# 2_Power_Switch.net
KiCad netlist of a schematic drawn in Altium Designer
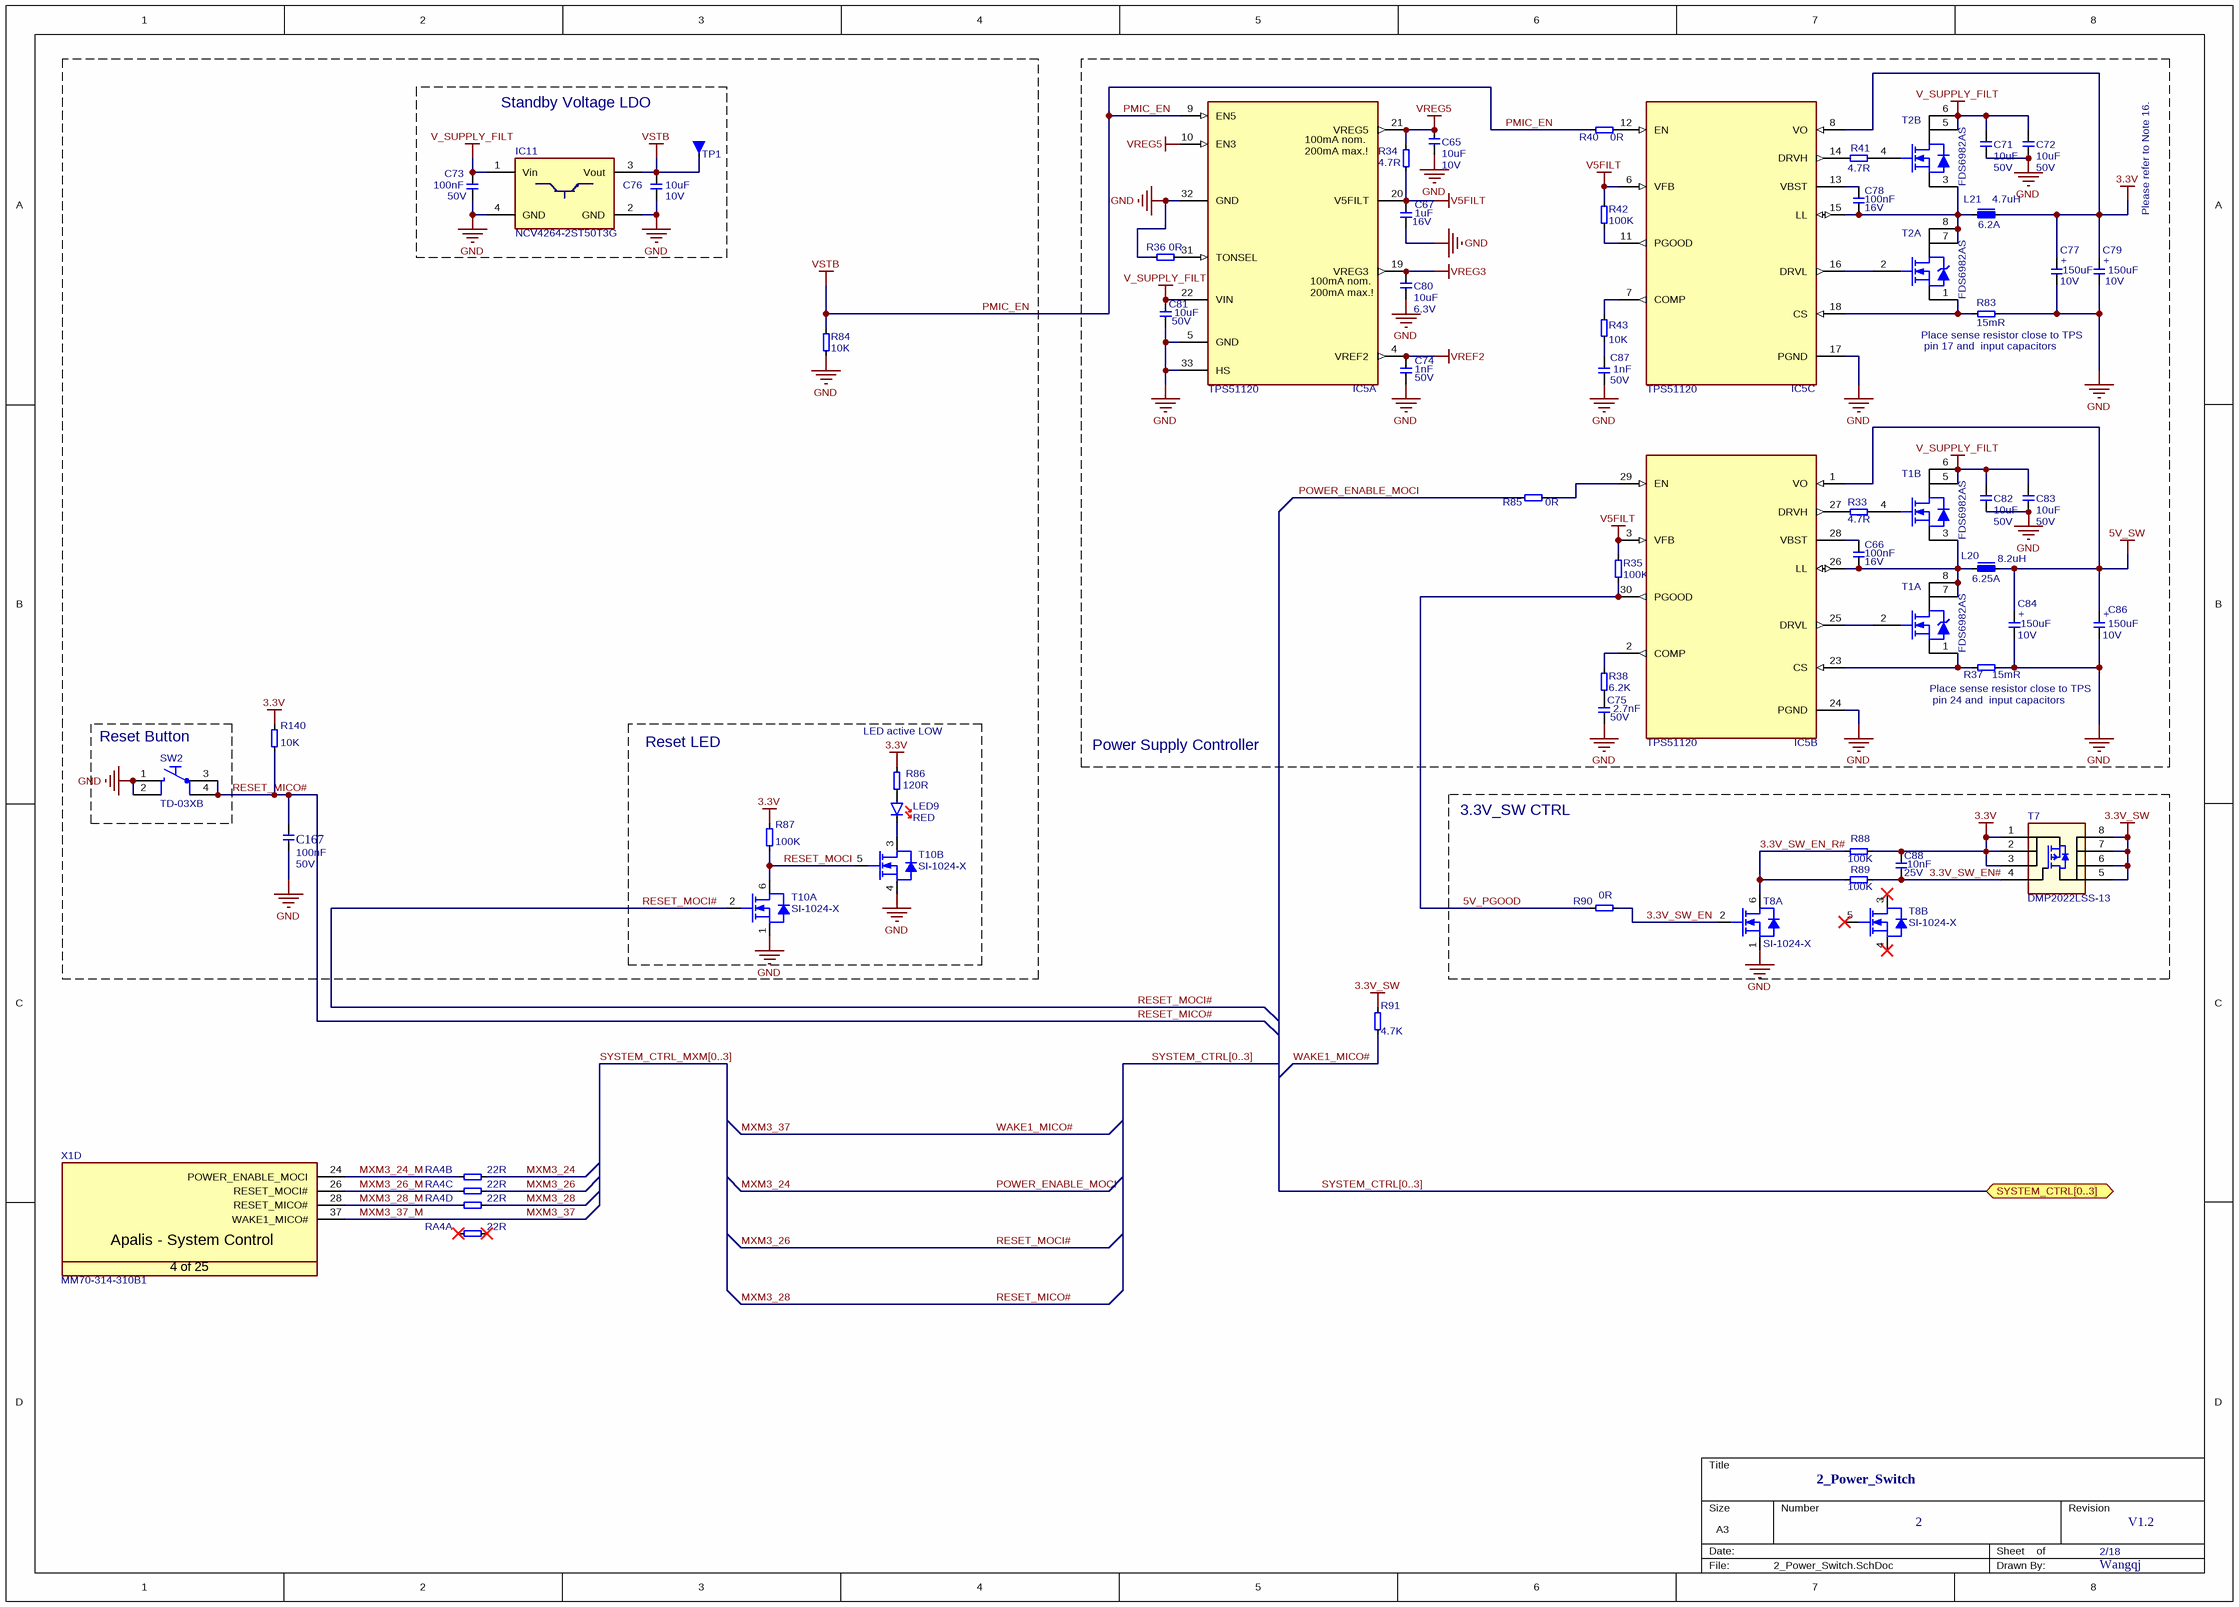
[diagram p0: 2_Power_Switch.SchDoc]

(export (version "E")
  (design (tool "Eeschema 10.0.6"))
  (components
    (comp (ref "C65")
      (value "10uF")
      (footprint "T_CAPC0805X125N")
      (description "Capacitor Ceramic X5R 10uF 10V 20% 0805")
      (fields (field (name "TOLERANCE") "20%") (field (name "RATING") "10V"))
      (libsource (lib "Apalis Evaluation Board") (part "C-X5R-10uF-10V-20%-0805"))
    )
    (comp (ref "C66")
      (value "100nF")
      (footprint "T_CAPC0603X33N")
      (description "Capacitor Ceramic X7R 100nF 16V 10% 0603")
      (fields (field (name "TOLERANCE") "10%") (field (name "RATING") "16V"))
      (libsource (lib "Apalis Evaluation Board") (part "C-X7R-100nF-16V-10%-0603"))
    )
    (comp (ref "C67")
      (value "1uF")
      (footprint "T_CAPC0603X33N")
      (description "Capacitor Ceramic X5R 1uF 16V 20% 0603")
      (fields (field (name "TOLERANCE") "20%") (field (name "RATING") "16V"))
      (libsource (lib "Apalis Evaluation Board") (part "C-X5R-1uF-16V-20%-0603"))
    )
    (comp (ref "C71")
      (value "10uF")
      (footprint "CAPC3225X160N")
      (description "Capacitor Ceramic X5R 10uF 50V 20% 1210")
      (fields (field (name "TOLERANCE") "20%") (field (name "RATING") "50V"))
      (libsource (lib "Apalis Evaluation Board") (part "C-X5R-10uF-50V-20%-1210"))
    )
    (comp (ref "C72")
      (value "10uF")
      (footprint "CAPC3225X160N")
      (description "Capacitor Ceramic X5R 10uF 50V 20% 1210")
      (fields (field (name "TOLERANCE") "20%") (field (name "RATING") "50V"))
      (libsource (lib "Apalis Evaluation Board") (part "C-X5R-10uF-50V-20%-1210"))
    )
    (comp (ref "C73")
      (value "100nF")
      (footprint "T_CAPC0603X33N")
      (description "Capacitor Ceramic X7R 100nF 50V 20% 0603")
      (fields (field (name "TOLERANCE") "20%") (field (name "RATING") "50V"))
      (libsource (lib "Apalis Evaluation Board") (part "C-X7R-100nF-50V-20%-0603"))
    )
    (comp (ref "C74")
      (value "1nF")
      (footprint "T_CAPC0603X33N")
      (description "Capacitor Ceramic X7R 1nF 50V 10% 0603")
      (fields (field (name "TOLERANCE") "10%") (field (name "RATING") "50V"))
      (libsource (lib "Apalis Evaluation Board") (part "C-X7R-1nF-50V-10%-0603"))
    )
    (comp (ref "C75")
      (value "2.7nF")
      (footprint "CAPC1005X60N")
      (description "Capacitor Ceramic X7R 2.7nF 50V 10% 0402")
      (fields (field (name "TOLERANCE") "10%") (field (name "RATING") "50V"))
      (libsource (lib "Apalis Evaluation Board") (part "C-X7R-2.7nF-50V-10%-0402"))
    )
    (comp (ref "C76")
      (value "10uF")
      (footprint "T_CAPC0805X125N")
      (description "Capacitor Ceramic X5R 10uF 10V 20% 0805")
      (fields (field (name "TOLERANCE") "20%") (field (name "RATING") "10V"))
      (libsource (lib "Apalis Evaluation Board") (part "C-X5R-10uF-10V-20%-0805"))
    )
    (comp (ref "C77")
      (value "150uF")
      (footprint "CAPMP7343X310N")
      (description "Capacitor TA 150uF 10V 10% 7343")
      (fields (field (name "TOLERANCE") "10%") (field (name "RATING") "10V"))
      (libsource (lib "Apalis Evaluation Board") (part "C-TA-150uF-10V-10%-7343"))
    )
    (comp (ref "C78")
      (value "100nF")
      (footprint "T_CAPC0603X33N")
      (description "Capacitor Ceramic X7R 100nF 16V 10% 0603")
      (fields (field (name "TOLERANCE") "10%") (field (name "RATING") "16V"))
      (libsource (lib "Apalis Evaluation Board") (part "C-X7R-100nF-16V-10%-0603"))
    )
    (comp (ref "C79")
      (value "150uF")
      (footprint "CAPMP7343X310N")
      (description "Capacitor TA 150uF 10V 10% 7343")
      (fields (field (name "TOLERANCE") "10%") (field (name "RATING") "10V"))
      (libsource (lib "Apalis Evaluation Board") (part "C-TA-150uF-10V-10%-7343"))
    )
    (comp (ref "C80")
      (value "10uF")
      (footprint "T_CAPC0603X33N")
      (description "Capacitor Ceramic X5R 10uF 6.3V 20% 0603")
      (fields (field (name "TOLERANCE") "20%") (field (name "RATING") "6.3V"))
      (libsource (lib "Apalis Evaluation Board") (part "C-X5R-10uF-6.3V-20%-0603"))
    )
    (comp (ref "C81")
      (value "10uF")
      (footprint "CAPC3225X160N")
      (description "Capacitor Ceramic X5R 10uF 50V 20% 1210")
      (fields (field (name "TOLERANCE") "20%") (field (name "RATING") "50V"))
      (libsource (lib "Apalis Evaluation Board") (part "C-X5R-10uF-50V-20%-1210"))
    )
    (comp (ref "C82")
      (value "10uF")
      (footprint "CAPC3225X160N")
      (description "Capacitor Ceramic X5R 10uF 50V 20% 1210")
      (fields (field (name "TOLERANCE") "20%") (field (name "RATING") "50V"))
      (libsource (lib "Apalis Evaluation Board") (part "C-X5R-10uF-50V-20%-1210"))
    )
    (comp (ref "C83")
      (value "10uF")
      (footprint "CAPC3225X160N")
      (description "Capacitor Ceramic X5R 10uF 50V 20% 1210")
      (fields (field (name "TOLERANCE") "20%") (field (name "RATING") "50V"))
      (libsource (lib "Apalis Evaluation Board") (part "C-X5R-10uF-50V-20%-1210"))
    )
    (comp (ref "C84")
      (value "150uF")
      (footprint "CAPMP7343X310N")
      (description "Capacitor TA 150uF 10V 10% 7343")
      (fields (field (name "TOLERANCE") "10%") (field (name "RATING") "10V"))
      (libsource (lib "Apalis Evaluation Board") (part "C-TA-150uF-10V-10%-7343"))
    )
    (comp (ref "C86")
      (value "150uF")
      (footprint "CAPMP7343X310N")
      (description "Capacitor TA 150uF 10V 10% 7343")
      (fields (field (name "TOLERANCE") "10%") (field (name "RATING") "10V"))
      (libsource (lib "Apalis Evaluation Board") (part "C-TA-150uF-10V-10%-7343"))
    )
    (comp (ref "C87")
      (value "1nF")
      (footprint "T_CAPC0603X33N")
      (description "Capacitor Ceramic X7R 1nF 50V 10% 0603")
      (fields (field (name "TOLERANCE") "10%") (field (name "RATING") "50V"))
      (libsource (lib "Apalis Evaluation Board") (part "C-X7R-1nF-50V-10%-0603"))
    )
    (comp (ref "C88")
      (value "10nF")
      (footprint "T_CAPC0603X33N")
      (description "Capacitor Ceramic X7R 10nF 25V 10% 0603")
      (fields (field (name "TOLERANCE") "10%") (field (name "RATING") "25V"))
      (libsource (lib "Apalis Evaluation Board") (part "C-X7R-10nF-25V-10%-0603"))
    )
    (comp (ref "C167")
      (value "100nF")
      (footprint "T_CAPC0603X33N")
      (description "Capacitor Ceramic X7R 100nF 50V 20% 0603")
      (fields (field (name "TOLERANCE") "20%") (field (name "RATING") "50V"))
      (libsource (lib "Apalis Evaluation Board") (part "C-100nF-50V-20%-0603-X7R"))
    )
    (comp (ref "IC5")
      (value "TPS51120")
      (footprint "QFN50P500X500X100-33N")
      (description "Power Supply Controller")
      (fields (field (name "MANUFACTURER PART NO.") "TPS51120"))
      (libsource (lib "Apalis Evaluation Board") (part "IC-TI-TPS51120"))
    )
    (comp (ref "IC11")
      (value "NCV4264-2ST50T3G")
      (footprint "T_ON_NCV4264-2ST50T3G")
      (description "NCV4264-2ST50T3G LDO Regulator")
      (fields (field (name "MANUFACTURER PART NO.") "NCV4264-2ST50T3G"))
      (libsource (lib "Apalis Evaluation Board") (part "IC-ON-NCV4264-2ST50T3G"))
    )
    (comp (ref "L20")
      (value "8.2uH")
      (footprint "T_INDM120120X80N")
      (description "Inductance 8.2uH 6.25A 20%")
      (fields
        (field (name "TOLERANCE") "20%")
        (field (name "MANUFACTURER PART NO.") "744771008")
        (field (name "RATING") "6.25A")
      )
      (libsource (lib "Apalis Evaluation Board") (part "L-Wurth-744771008-8.2uH-6.25A-20%"))
    )
    (comp (ref "L21")
      (value "4.7uH")
      (footprint "T_INDM102102X45N")
      (description "Inductance 4.7uH 6.2A 20%")
      (fields
        (field (name "TOLERANCE") "20%")
        (field (name "MANUFACTURER PART NO.") "7447797470")
        (field (name "RATING") "6.2A")
      )
      (libsource (lib "Apalis Evaluation Board") (part "L-Wurth-7447797470-4.7uH-6.2A-20%"))
    )
    (comp (ref "LED9")
      (value "LS T670-K1L2-1")
      (footprint "LC-0805_LED_S3")
      (description "LED red, Osram LS T670-K1L2-1")
      (fields (field (name "COLOR") "RED"))
      (libsource (lib "Apalis Evaluation Board") (part "LED-Osram-LS T670-K1L2-1"))
    )
    (comp (ref "R33")
      (value "4.7R")
      (footprint "RESC1005X40N")
      (description "Resistor 4.7 ohm 63mW 5% 0402")
      (fields (field (name "TOLERANCE") "5%"))
      (libsource (lib "Apalis Evaluation Board") (part "R-4.7R-63mW-5%-0402"))
    )
    (comp (ref "R34")
      (value "4.7R")
      (footprint "RESC1005X40N")
      (description "Resistor 4.7 ohm 63mW 5% 0402")
      (fields (field (name "TOLERANCE") "5%"))
      (libsource (lib "Apalis Evaluation Board") (part "R-4.7R-63mW-5%-0402"))
    )
    (comp (ref "R35")
      (value "100K")
      (footprint "T_RESC0603X30N")
      (description "Resistor 100 Kohm 63mW 5% 0603")
      (fields (field (name "TOLERANCE") "5%"))
      (libsource (lib "Apalis Evaluation Board") (part "R-100KR-63mW-5%-0603"))
    )
    (comp (ref "R36")
      (value "0R")
      (footprint "T_RESC0603X30N")
      (description "Resistor 0 ohm 63mW 1% 0603")
      (fields (field (name "TOLERANCE") "1%"))
      (libsource (lib "Apalis Evaluation Board") (part "R-0R-63mW-1%-0603"))
    )
    (comp (ref "R37")
      (value "15mR")
      (footprint "RESC3316X76N")
      (description "Resistor 15 mohm 250mW 1% 1206")
      (fields (field (name "TOLERANCE") "1%"))
      (libsource (lib "Apalis Evaluation Board") (part "R-15mR-250mW-1%-1206"))
    )
    (comp (ref "R38")
      (value "6.2K")
      (footprint "RESC1005X40N")
      (description "Resistor 6.2 Kohm 63mW 1% 0402")
      (fields (field (name "TOLERANCE") "1%"))
      (libsource (lib "Apalis Evaluation Board") (part "R-6.2KR-63mW-1%-0402"))
    )
    (comp (ref "R40")
      (value "0R")
      (footprint "T_RESC0603X30N")
      (description "Resistor 0 ohm 63mW 1% 0603")
      (fields (field (name "TOLERANCE") "1%"))
      (libsource (lib "Apalis Evaluation Board") (part "R-0R-63mW-1%-0603"))
    )
    (comp (ref "R41")
      (value "4.7R")
      (footprint "RESC1005X40N")
      (description "Resistor 4.7 ohm 63mW 5% 0402")
      (fields (field (name "TOLERANCE") "5%"))
      (libsource (lib "Apalis Evaluation Board") (part "R-4.7R-63mW-5%-0402"))
    )
    (comp (ref "R42")
      (value "100K")
      (footprint "T_RESC0603X30N")
      (description "Resistor 100 Kohm 63mW 5% 0603")
      (fields (field (name "TOLERANCE") "5%"))
      (libsource (lib "Apalis Evaluation Board") (part "R-100KR-63mW-5%-0603"))
    )
    (comp (ref "R43")
      (value "10K")
      (footprint "T_RESC0603X30N")
      (description "Resistor 10 Kohm 63mW 1% 0603")
      (fields (field (name "TOLERANCE") "1%"))
      (libsource (lib "Apalis Evaluation Board") (part "R-10KR-63mW-1%-0603"))
    )
    (comp (ref "R83")
      (value "15mR")
      (footprint "RESC3316X76N")
      (description "Resistor 15 mohm 250mW 1% 1206")
      (fields (field (name "TOLERANCE") "1%"))
      (libsource (lib "Apalis Evaluation Board") (part "R-15mR-250mW-1%-1206"))
    )
    (comp (ref "R84")
      (value "10K")
      (footprint "T_RESC0603X30N")
      (description "Resistor 10 Kohm 63mW 5% 0603")
      (fields (field (name "TOLERANCE") "5%"))
      (libsource (lib "Apalis Evaluation Board") (part "R-10KR-63mW-5%-0603"))
    )
    (comp (ref "R85")
      (value "0R")
      (footprint "T_RESC0603X30N")
      (description "Resistor 0 ohm 63mW 1% 0603")
      (fields (field (name "TOLERANCE") "1%"))
      (libsource (lib "Apalis Evaluation Board") (part "R-0R-63mW-1%-0603"))
    )
    (comp (ref "R86")
      (value "120R")
      (footprint "T_RESC0603X30N")
      (description "Resistor 120 ohm 63mW 5% 0603")
      (fields (field (name "TOLERANCE") "5%"))
      (libsource (lib "Apalis Evaluation Board") (part "R-120R-63mW-5%-0603"))
    )
    (comp (ref "R87")
      (value "100K")
      (footprint "T_RESC0603X30N")
      (description "Resistor 100 Kohm 63mW 5% 0603")
      (fields (field (name "TOLERANCE") "5%"))
      (libsource (lib "Apalis Evaluation Board") (part "R-100KR-63mW-5%-0603"))
    )
    (comp (ref "R88")
      (value "100K")
      (footprint "T_RESC0603X30N")
      (description "Resistor 100 Kohm 63mW 5% 0603")
      (fields (field (name "TOLERANCE") "5%"))
      (libsource (lib "Apalis Evaluation Board") (part "R-100KR-63mW-5%-0603"))
    )
    (comp (ref "R89")
      (value "100K")
      (footprint "T_RESC0603X30N")
      (description "Resistor 100 Kohm 63mW 5% 0603")
      (fields (field (name "TOLERANCE") "5%"))
      (libsource (lib "Apalis Evaluation Board") (part "R-100KR-63mW-5%-0603"))
    )
    (comp (ref "R90")
      (value "0R")
      (footprint "T_RESC0603X30N")
      (description "Resistor 0 ohm 63mW 1% 0603")
      (fields (field (name "TOLERANCE") "1%"))
      (libsource (lib "Apalis Evaluation Board") (part "R-0R-63mW-1%-0603"))
    )
    (comp (ref "R91")
      (value "4.7K")
      (footprint "t_RESC0603X30N")
      (description "Resistor 4.7 Kohm 63mW 5% 0603")
      (fields (field (name "TOLERANCE") "5%"))
      (libsource (lib "Apalis Evaluation Board") (part "R-4.7kR-63mW-5%-0603"))
    )
    (comp (ref "R140")
      (value "10K")
      (footprint "0805R")
      (description "Resistor 100 Kohm 63mW 5% 0603")
      (fields (field (name "TOLERANCE") "5%"))
      (libsource (lib "Apalis Evaluation Board") (part "R-100KR-63mW-5%-0603"))
    )
    (comp (ref "RA4")
      (value "22R")
      (footprint "T_Resistor_Array_X4")
      (description "Resistor Array 22 R 63mW 5% 1206")
      (fields (field (name "TOLERANCE") "5%"))
      (libsource (lib "Apalis Evaluation Board") (part "RA-22R-63mW-5%-1206-div"))
    )
    (comp (ref "SW2")
      (value "TD-03XB")
      (footprint "T_WMF_TD-03XB")
      (description "Push Button")
      (libsource (lib "Apalis Evaluation Board") (part "SW-WMF-TD-03XB"))
    )
    (comp (ref "T1")
      (value "FDS6982AS")
      (footprint "SOIC127P600X173-8N")
      (description "N-Channel PowerTrench SyncFET")
      (fields (field (name "MANUFACTURER PART NO.") "FDS6982AS"))
      (libsource (lib "Apalis Evaluation Board") (part "T-Fairchild-FDS6982AS-N"))
    )
    (comp (ref "T2")
      (value "FDS6982AS")
      (footprint "SOIC127P600X173-8N")
      (description "N-Channel PowerTrench SyncFET")
      (fields (field (name "MANUFACTURER PART NO.") "FDS6982AS"))
      (libsource (lib "Apalis Evaluation Board") (part "T-Fairchild-FDS6982AS-N"))
    )
    (comp (ref "T7")
      (value "DMP2022LSS-13")
      (footprint "SOIC127P600X173-8N")
      (description "p-channel MOSFET, DMP2022LSS-13")
      (fields (field (name "MANUFACTURER PART NO.") "DMP2022LSS-13"))
      (libsource (lib "Apalis Evaluation Board") (part "T-Diodes-DMP2022LSS-13-8-SOIC"))
    )
    (comp (ref "T8")
      (value "T-Vishay-SI-1024X-N")
      (footprint "SOTFL50P160X60-6N")
      (description "Dual N-Channel 20V (D-S)  MOSFET")
      (fields (field (name "MANUFACTURER PART NO.") "SI-1024-X"))
      (libsource (lib "Apalis Evaluation Board") (part "T-Vishay-SI-1024X-N"))
    )
    (comp (ref "T10")
      (value "T-Vishay-SI-1024X-N")
      (footprint "SOTFL50P160X60-6N")
      (description "Dual N-Channel 20V (D-S)  MOSFET")
      (fields (field (name "MANUFACTURER PART NO.") "SI-1024-X"))
      (libsource (lib "Apalis Evaluation Board") (part "T-Vishay-SI-1024X-N"))
    )
    (comp (ref "TP1")
      (value "Testpin")
      (footprint "T_TP-THT")
      (description "Testpin TH")
      (libsource (lib "Apalis Evaluation Board") (part "Testpin"))
    )
    (comp (ref "X1")
      (value "CON-JAE-MM70-314-310B1-314-0.5mm")
      (footprint "T_JAE_MM70-314-310B1")
      (description "MXM3 Connector")
      (fields (field (name "MANUFACTURER PART NO.") "MM70-314-310B1"))
      (libsource (lib "Apalis Evaluation Board") (part "CON-JAE-MM70-314-310B1-314-0.5mm"))
    )
  )
  (nets
    (net (code "9") (name "/3.3V_SW_EN") (class "Default")
      (node (ref "R90") (pin "1") (pinfunction "1_1") (pintype "passive"))
      (node (ref "T8") (pin "2") (pinfunction "G_2") (pintype "passive"))
    )
    (net (code "10") (name "/3.3V_SW_EN#") (class "Default")
      (node (ref "C88") (pin "1") (pinfunction "1_1") (pintype "passive"))
      (node (ref "R89") (pin "1") (pinfunction "1_1") (pintype "passive"))
      (node (ref "T7") (pin "4") (pinfunction "G_4") (pintype "passive"))
    )
    (net (code "11") (name "/3.3V_SW_EN_R#") (class "Default")
      (node (ref "R88") (pin "2") (pinfunction "2_2") (pintype "passive"))
      (node (ref "R89") (pin "2") (pinfunction "2_2") (pintype "passive"))
      (node (ref "T8") (pin "6") (pinfunction "D_6") (pintype "passive"))
    )
    (net (code "12") (name "/5V_PGOOD") (class "Default")
      (node (ref "IC5") (pin "30") (pinfunction "PGOOD_30") (pintype "output"))
      (node (ref "R35") (pin "1") (pinfunction "1_1") (pintype "passive"))
      (node (ref "R90") (pin "2") (pinfunction "2_2") (pintype "passive"))
    )
    (net (code "13") (name "/MXM3_24") (class "Default")
      (node (ref "R85") (pin "1") (pinfunction "1_1") (pintype "passive"))
      (node (ref "RA4") (pin "6") (pinfunction "6_6") (pintype "passive"))
    )
    (net (code "14") (name "/MXM3_24_M") (class "Default")
      (node (ref "RA4") (pin "2") (pinfunction "2_2") (pintype "passive"))
      (node (ref "X1") (pin "24") (pinfunction "POWER_ENABLE_MOCI_24") (pintype "passive"))
    )
    (net (code "15") (name "/MXM3_26") (class "Default")
      (node (ref "RA4") (pin "7") (pinfunction "7_7") (pintype "passive"))
      (node (ref "T10") (pin "2") (pinfunction "G_2") (pintype "passive"))
    )
    (net (code "16") (name "/MXM3_26_M") (class "Default")
      (node (ref "RA4") (pin "3") (pinfunction "3_3") (pintype "passive"))
      (node (ref "X1") (pin "26") (pinfunction "RESET_MOCI#_26") (pintype "passive"))
    )
    (net (code "17") (name "/MXM3_28") (class "Default")
      (node (ref "C167") (pin "2") (pinfunction "2_2") (pintype "passive"))
      (node (ref "R140") (pin "1") (pinfunction "1_1") (pintype "passive"))
      (node (ref "RA4") (pin "8") (pinfunction "8_8") (pintype "passive"))
      (node (ref "SW2") (pin "3") (pinfunction "3_3") (pintype "passive"))
      (node (ref "SW2") (pin "4") (pinfunction "4_4") (pintype "passive"))
    )
    (net (code "18") (name "/MXM3_28_M") (class "Default")
      (node (ref "RA4") (pin "4") (pinfunction "4_4") (pintype "passive"))
      (node (ref "X1") (pin "28") (pinfunction "RESET_MICO#_28") (pintype "passive"))
    )
    (net (code "19") (name "/MXM3_37") (class "Default")
      (node (ref "R91") (pin "2") (pinfunction "2_2") (pintype "passive"))
      (node (ref "X1") (pin "37") (pinfunction "WAKE1_MICO#_37") (pintype "passive"))
    )
    (net (code "20") (name "/RESET_MOCI") (class "Default")
      (node (ref "R87") (pin "1") (pinfunction "1_1") (pintype "passive"))
      (node (ref "T10") (pin "5") (pinfunction "G_5") (pintype "passive"))
      (node (ref "T10") (pin "6") (pinfunction "D_6") (pintype "passive"))
    )
    (net (code "23") (name "3.3V") (class "Default")
      (node (ref "C77") (pin "1") (pinfunction "1_1") (pintype "passive"))
      (node (ref "C79") (pin "1") (pinfunction "1_1") (pintype "passive"))
      (node (ref "C88") (pin "2") (pinfunction "2_2") (pintype "passive"))
      (node (ref "IC5") (pin "8") (pinfunction "VO_8") (pintype "input"))
      (node (ref "L21") (pin "2") (pinfunction "2_2") (pintype "passive"))
      (node (ref "R140") (pin "2") (pinfunction "2_2") (pintype "passive"))
      (node (ref "R86") (pin "2") (pinfunction "2_2") (pintype "passive"))
      (node (ref "R87") (pin "2") (pinfunction "2_2") (pintype "passive"))
      (node (ref "R88") (pin "1") (pinfunction "1_1") (pintype "passive"))
      (node (ref "T7") (pin "1") (pinfunction "S_1") (pintype "passive"))
      (node (ref "T7") (pin "2") (pinfunction "S_2") (pintype "passive"))
      (node (ref "T7") (pin "3") (pinfunction "S_3") (pintype "passive"))
    )
    (net (code "24") (name "3.3V_SW") (class "Default")
      (node (ref "R91") (pin "1") (pinfunction "1_1") (pintype "passive"))
      (node (ref "T7") (pin "5") (pinfunction "D_5") (pintype "passive"))
      (node (ref "T7") (pin "6") (pinfunction "D_6") (pintype "passive"))
      (node (ref "T7") (pin "7") (pinfunction "D_7") (pintype "passive"))
      (node (ref "T7") (pin "8") (pinfunction "D_8") (pintype "passive"))
    )
    (net (code "25") (name "5V_SW") (class "Default")
      (node (ref "C84") (pin "1") (pinfunction "1_1") (pintype "passive"))
      (node (ref "C86") (pin "1") (pinfunction "1_1") (pintype "passive"))
      (node (ref "IC5") (pin "1") (pinfunction "VO_1") (pintype "input"))
      (node (ref "L20") (pin "2") (pinfunction "2_2") (pintype "passive"))
    )
    (net (code "26") (name "GND") (class "Default")
      (node (ref "C167") (pin "1") (pinfunction "1_1") (pintype "passive"))
      (node (ref "C65") (pin "1") (pinfunction "1_1") (pintype "passive"))
      (node (ref "C67") (pin "1") (pinfunction "1_1") (pintype "passive"))
      (node (ref "C71") (pin "1") (pinfunction "1_1") (pintype "passive"))
      (node (ref "C72") (pin "1") (pinfunction "1_1") (pintype "passive"))
      (node (ref "C73") (pin "1") (pinfunction "1_1") (pintype "passive"))
      (node (ref "C74") (pin "1") (pinfunction "1_1") (pintype "passive"))
      (node (ref "C75") (pin "1") (pinfunction "1_1") (pintype "passive"))
      (node (ref "C76") (pin "1") (pinfunction "1_1") (pintype "passive"))
      (node (ref "C77") (pin "2") (pinfunction "2_2") (pintype "passive"))
      (node (ref "C79") (pin "2") (pinfunction "2_2") (pintype "passive"))
      (node (ref "C80") (pin "1") (pinfunction "1_1") (pintype "passive"))
      (node (ref "C81") (pin "1") (pinfunction "1_1") (pintype "passive"))
      (node (ref "C82") (pin "1") (pinfunction "1_1") (pintype "passive"))
      (node (ref "C83") (pin "1") (pinfunction "1_1") (pintype "passive"))
      (node (ref "C84") (pin "2") (pinfunction "2_2") (pintype "passive"))
      (node (ref "C86") (pin "2") (pinfunction "2_2") (pintype "passive"))
      (node (ref "C87") (pin "1") (pinfunction "1_1") (pintype "passive"))
      (node (ref "IC11") (pin "2") (pinfunction "GND_2") (pintype "passive"))
      (node (ref "IC11") (pin "4") (pinfunction "GND_4") (pintype "passive"))
      (node (ref "IC5") (pin "17") (pinfunction "PGND_17") (pintype "power_in"))
      (node (ref "IC5") (pin "24") (pinfunction "PGND_24") (pintype "power_in"))
      (node (ref "IC5") (pin "32") (pinfunction "GND_32") (pintype "power_in"))
      (node (ref "IC5") (pin "33") (pinfunction "HS_33") (pintype "passive"))
      (node (ref "IC5") (pin "5") (pinfunction "GND_5") (pintype "power_in"))
      (node (ref "R36") (pin "1") (pinfunction "1_1") (pintype "passive"))
      (node (ref "R37") (pin "2") (pinfunction "2_2") (pintype "passive"))
      (node (ref "R83") (pin "2") (pinfunction "2_2") (pintype "passive"))
      (node (ref "R84") (pin "1") (pinfunction "1_1") (pintype "passive"))
      (node (ref "SW2") (pin "1") (pinfunction "1_1") (pintype "passive"))
      (node (ref "SW2") (pin "2") (pinfunction "2_2") (pintype "passive"))
      (node (ref "T10") (pin "1") (pinfunction "S_1") (pintype "passive"))
      (node (ref "T10") (pin "4") (pinfunction "S_4") (pintype "passive"))
      (node (ref "T8") (pin "1") (pinfunction "S_1") (pintype "passive"))
    )
    (net (code "27") (name "Net-(C75-Pad2)") (class "Default")
      (node (ref "C75") (pin "2") (pinfunction "2_2") (pintype "passive"))
      (node (ref "R38") (pin "1") (pinfunction "1_1") (pintype "passive"))
    )
    (net (code "28") (name "Net-(C87-Pad2)") (class "Default")
      (node (ref "C87") (pin "2") (pinfunction "2_2") (pintype "passive"))
      (node (ref "R43") (pin "1") (pinfunction "1_1") (pintype "passive"))
    )
    (net (code "29") (name "Net-(IC5A-TONSEL)") (class "Default")
      (node (ref "IC5") (pin "31") (pinfunction "TONSEL_31") (pintype "input"))
      (node (ref "R36") (pin "2") (pinfunction "2_2") (pintype "passive"))
    )
    (net (code "30") (name "Net-(IC5B-COMP)") (class "Default")
      (node (ref "IC5") (pin "2") (pinfunction "COMP_2") (pintype "output"))
      (node (ref "R38") (pin "2") (pinfunction "2_2") (pintype "passive"))
    )
    (net (code "31") (name "Net-(IC5B-CS)") (class "Default")
      (node (ref "IC5") (pin "23") (pinfunction "CS_23") (pintype "input"))
      (node (ref "R37") (pin "1") (pinfunction "1_1") (pintype "passive"))
      (node (ref "T1") (pin "1") (pinfunction "S_1") (pintype "passive"))
    )
    (net (code "32") (name "Net-(IC5B-DRVH)") (class "Default")
      (node (ref "IC5") (pin "27") (pinfunction "DRVH_27") (pintype "output"))
      (node (ref "R33") (pin "1") (pinfunction "1_1") (pintype "passive"))
    )
    (net (code "33") (name "Net-(IC5B-DRVL)") (class "Default")
      (node (ref "IC5") (pin "25") (pinfunction "DRVL_25") (pintype "output"))
      (node (ref "T1") (pin "2") (pinfunction "G_2") (pintype "passive"))
    )
    (net (code "34") (name "Net-(IC5B-EN)") (class "Default")
      (node (ref "IC5") (pin "29") (pinfunction "EN_29") (pintype "input"))
      (node (ref "R85") (pin "2") (pinfunction "2_2") (pintype "passive"))
    )
    (net (code "35") (name "Net-(IC5B-LL)") (class "Default")
      (node (ref "C66") (pin "1") (pinfunction "1_1") (pintype "passive"))
      (node (ref "IC5") (pin "26") (pinfunction "LL_26") (pintype "bidirectional"))
      (node (ref "L20") (pin "1") (pinfunction "1_1") (pintype "passive"))
      (node (ref "T1") (pin "3") (pinfunction "S_3") (pintype "passive"))
      (node (ref "T1") (pin "7") (pinfunction "D_7") (pintype "passive"))
      (node (ref "T1") (pin "8") (pinfunction "D_8") (pintype "passive"))
    )
    (net (code "36") (name "Net-(IC5B-VBST)") (class "Default")
      (node (ref "C66") (pin "2") (pinfunction "2_2") (pintype "passive"))
      (node (ref "IC5") (pin "28") (pinfunction "VBST_28") (pintype "power_in"))
    )
    (net (code "37") (name "Net-(IC5C-COMP)") (class "Default")
      (node (ref "IC5") (pin "7") (pinfunction "COMP_7") (pintype "output"))
      (node (ref "R43") (pin "2") (pinfunction "2_2") (pintype "passive"))
    )
    (net (code "38") (name "Net-(IC5C-CS)") (class "Default")
      (node (ref "IC5") (pin "18") (pinfunction "CS_18") (pintype "input"))
      (node (ref "R83") (pin "1") (pinfunction "1_1") (pintype "passive"))
      (node (ref "T2") (pin "1") (pinfunction "S_1") (pintype "passive"))
    )
    (net (code "39") (name "Net-(IC5C-DRVH)") (class "Default")
      (node (ref "IC5") (pin "14") (pinfunction "DRVH_14") (pintype "output"))
      (node (ref "R41") (pin "1") (pinfunction "1_1") (pintype "passive"))
    )
    (net (code "40") (name "Net-(IC5C-DRVL)") (class "Default")
      (node (ref "IC5") (pin "16") (pinfunction "DRVL_16") (pintype "output"))
      (node (ref "T2") (pin "2") (pinfunction "G_2") (pintype "passive"))
    )
    (net (code "41") (name "Net-(IC5C-EN)") (class "Default")
      (node (ref "IC5") (pin "12") (pinfunction "EN_12") (pintype "input"))
      (node (ref "R40") (pin "2") (pinfunction "2_2") (pintype "passive"))
    )
    (net (code "42") (name "Net-(IC5C-LL)") (class "Default")
      (node (ref "C78") (pin "1") (pinfunction "1_1") (pintype "passive"))
      (node (ref "IC5") (pin "15") (pinfunction "LL_15") (pintype "bidirectional"))
      (node (ref "L21") (pin "1") (pinfunction "1_1") (pintype "passive"))
      (node (ref "T2") (pin "3") (pinfunction "S_3") (pintype "passive"))
      (node (ref "T2") (pin "7") (pinfunction "D_7") (pintype "passive"))
      (node (ref "T2") (pin "8") (pinfunction "D_8") (pintype "passive"))
    )
    (net (code "43") (name "Net-(IC5C-PGOOD)") (class "Default")
      (node (ref "IC5") (pin "11") (pinfunction "PGOOD_11") (pintype "output"))
      (node (ref "R42") (pin "1") (pinfunction "1_1") (pintype "passive"))
    )
    (net (code "44") (name "Net-(IC5C-VBST)") (class "Default")
      (node (ref "C78") (pin "2") (pinfunction "2_2") (pintype "passive"))
      (node (ref "IC5") (pin "13") (pinfunction "VBST_13") (pintype "passive"))
    )
    (net (code "45") (name "Net-(LED9-PadA)") (class "Default")
      (node (ref "LED9") (pin "A") (pinfunction "A_A") (pintype "passive"))
      (node (ref "R86") (pin "1") (pinfunction "1_1") (pintype "passive"))
    )
    (net (code "46") (name "Net-(T1B-G)") (class "Default")
      (node (ref "R33") (pin "2") (pinfunction "2_2") (pintype "passive"))
      (node (ref "T1") (pin "4") (pinfunction "G_4") (pintype "passive"))
    )
    (net (code "47") (name "Net-(T2B-G)") (class "Default")
      (node (ref "R41") (pin "2") (pinfunction "2_2") (pintype "passive"))
      (node (ref "T2") (pin "4") (pinfunction "G_4") (pintype "passive"))
    )
    (net (code "48") (name "Net-(T10B-D)") (class "Default")
      (node (ref "LED9") (pin "K") (pinfunction "K_K") (pintype "passive"))
      (node (ref "T10") (pin "3") (pinfunction "D_3") (pintype "passive"))
    )
    (net (code "49") (name "V5FILT") (class "Default")
      (node (ref "C67") (pin "2") (pinfunction "2_2") (pintype "passive"))
      (node (ref "IC5") (pin "20") (pinfunction "V5FILT_20") (pintype "power_in"))
      (node (ref "IC5") (pin "3") (pinfunction "VFB_3") (pintype "input"))
      (node (ref "IC5") (pin "6") (pinfunction "VFB_6") (pintype "input"))
      (node (ref "R34") (pin "1") (pinfunction "1_1") (pintype "passive"))
      (node (ref "R35") (pin "2") (pinfunction "2_2") (pintype "passive"))
      (node (ref "R42") (pin "2") (pinfunction "2_2") (pintype "passive"))
    )
    (net (code "50") (name "VREF2") (class "Default")
      (node (ref "C74") (pin "2") (pinfunction "2_2") (pintype "passive"))
      (node (ref "IC5") (pin "4") (pinfunction "VREF2_4") (pintype "output"))
    )
    (net (code "51") (name "VREG3") (class "Default")
      (node (ref "C80") (pin "2") (pinfunction "2_2") (pintype "passive"))
      (node (ref "IC5") (pin "19") (pinfunction "VREG3_19") (pintype "output"))
    )
    (net (code "52") (name "VREG5") (class "Default")
      (node (ref "C65") (pin "2") (pinfunction "2_2") (pintype "passive"))
      (node (ref "IC5") (pin "10") (pinfunction "EN3_10") (pintype "input"))
      (node (ref "IC5") (pin "21") (pinfunction "VREG5_21") (pintype "output"))
      (node (ref "R34") (pin "2") (pinfunction "2_2") (pintype "passive"))
    )
    (net (code "53") (name "VSTB") (class "Default")
      (node (ref "C76") (pin "2") (pinfunction "2_2") (pintype "passive"))
      (node (ref "IC11") (pin "3") (pinfunction "Vout_3") (pintype "passive"))
      (node (ref "IC5") (pin "9") (pinfunction "EN5_9") (pintype "input"))
      (node (ref "R40") (pin "1") (pinfunction "1_1") (pintype "passive"))
      (node (ref "R84") (pin "2") (pinfunction "2_2") (pintype "passive"))
      (node (ref "TP1") (pin "1") (pinfunction "1_1") (pintype "passive"))
    )
    (net (code "54") (name "V_SUPPLY_FILT") (class "Default")
      (node (ref "C71") (pin "2") (pinfunction "2_2") (pintype "passive"))
      (node (ref "C72") (pin "2") (pinfunction "2_2") (pintype "passive"))
      (node (ref "C73") (pin "2") (pinfunction "2_2") (pintype "passive"))
      (node (ref "C81") (pin "2") (pinfunction "2_2") (pintype "passive"))
      (node (ref "C82") (pin "2") (pinfunction "2_2") (pintype "passive"))
      (node (ref "C83") (pin "2") (pinfunction "2_2") (pintype "passive"))
      (node (ref "IC11") (pin "1") (pinfunction "Vin_1") (pintype "passive"))
      (node (ref "IC5") (pin "22") (pinfunction "VIN_22") (pintype "power_in"))
      (node (ref "T1") (pin "5") (pinfunction "D_5") (pintype "passive"))
      (node (ref "T1") (pin "6") (pinfunction "D_6") (pintype "passive"))
      (node (ref "T2") (pin "5") (pinfunction "D_5") (pintype "passive"))
      (node (ref "T2") (pin "6") (pinfunction "D_6") (pintype "passive"))
    )
    (net (code "55") (name "unconnected-(RA4-Pad1)") (class "Default")
      (node (ref "RA4") (pin "1") (pinfunction "1_1") (pintype "passive+no_connect"))
    )
    (net (code "56") (name "unconnected-(RA4-Pad5)") (class "Default")
      (node (ref "RA4") (pin "5") (pinfunction "5_5") (pintype "passive+no_connect"))
    )
    (net (code "57") (name "unconnected-(T8B-D-Pad3)") (class "Default")
      (node (ref "T8") (pin "3") (pinfunction "D_3") (pintype "passive+no_connect"))
    )
    (net (code "58") (name "unconnected-(T8B-G-Pad5)") (class "Default")
      (node (ref "T8") (pin "5") (pinfunction "G_5") (pintype "passive+no_connect"))
    )
    (net (code "59") (name "unconnected-(T8B-S-Pad4)") (class "Default")
      (node (ref "T8") (pin "4") (pinfunction "S_4") (pintype "passive+no_connect"))
    )
  )
)
